# Addon-mapleCUx_HM-RFM69-012.net
KiCad netlist of a schematic drawn in EAGLE
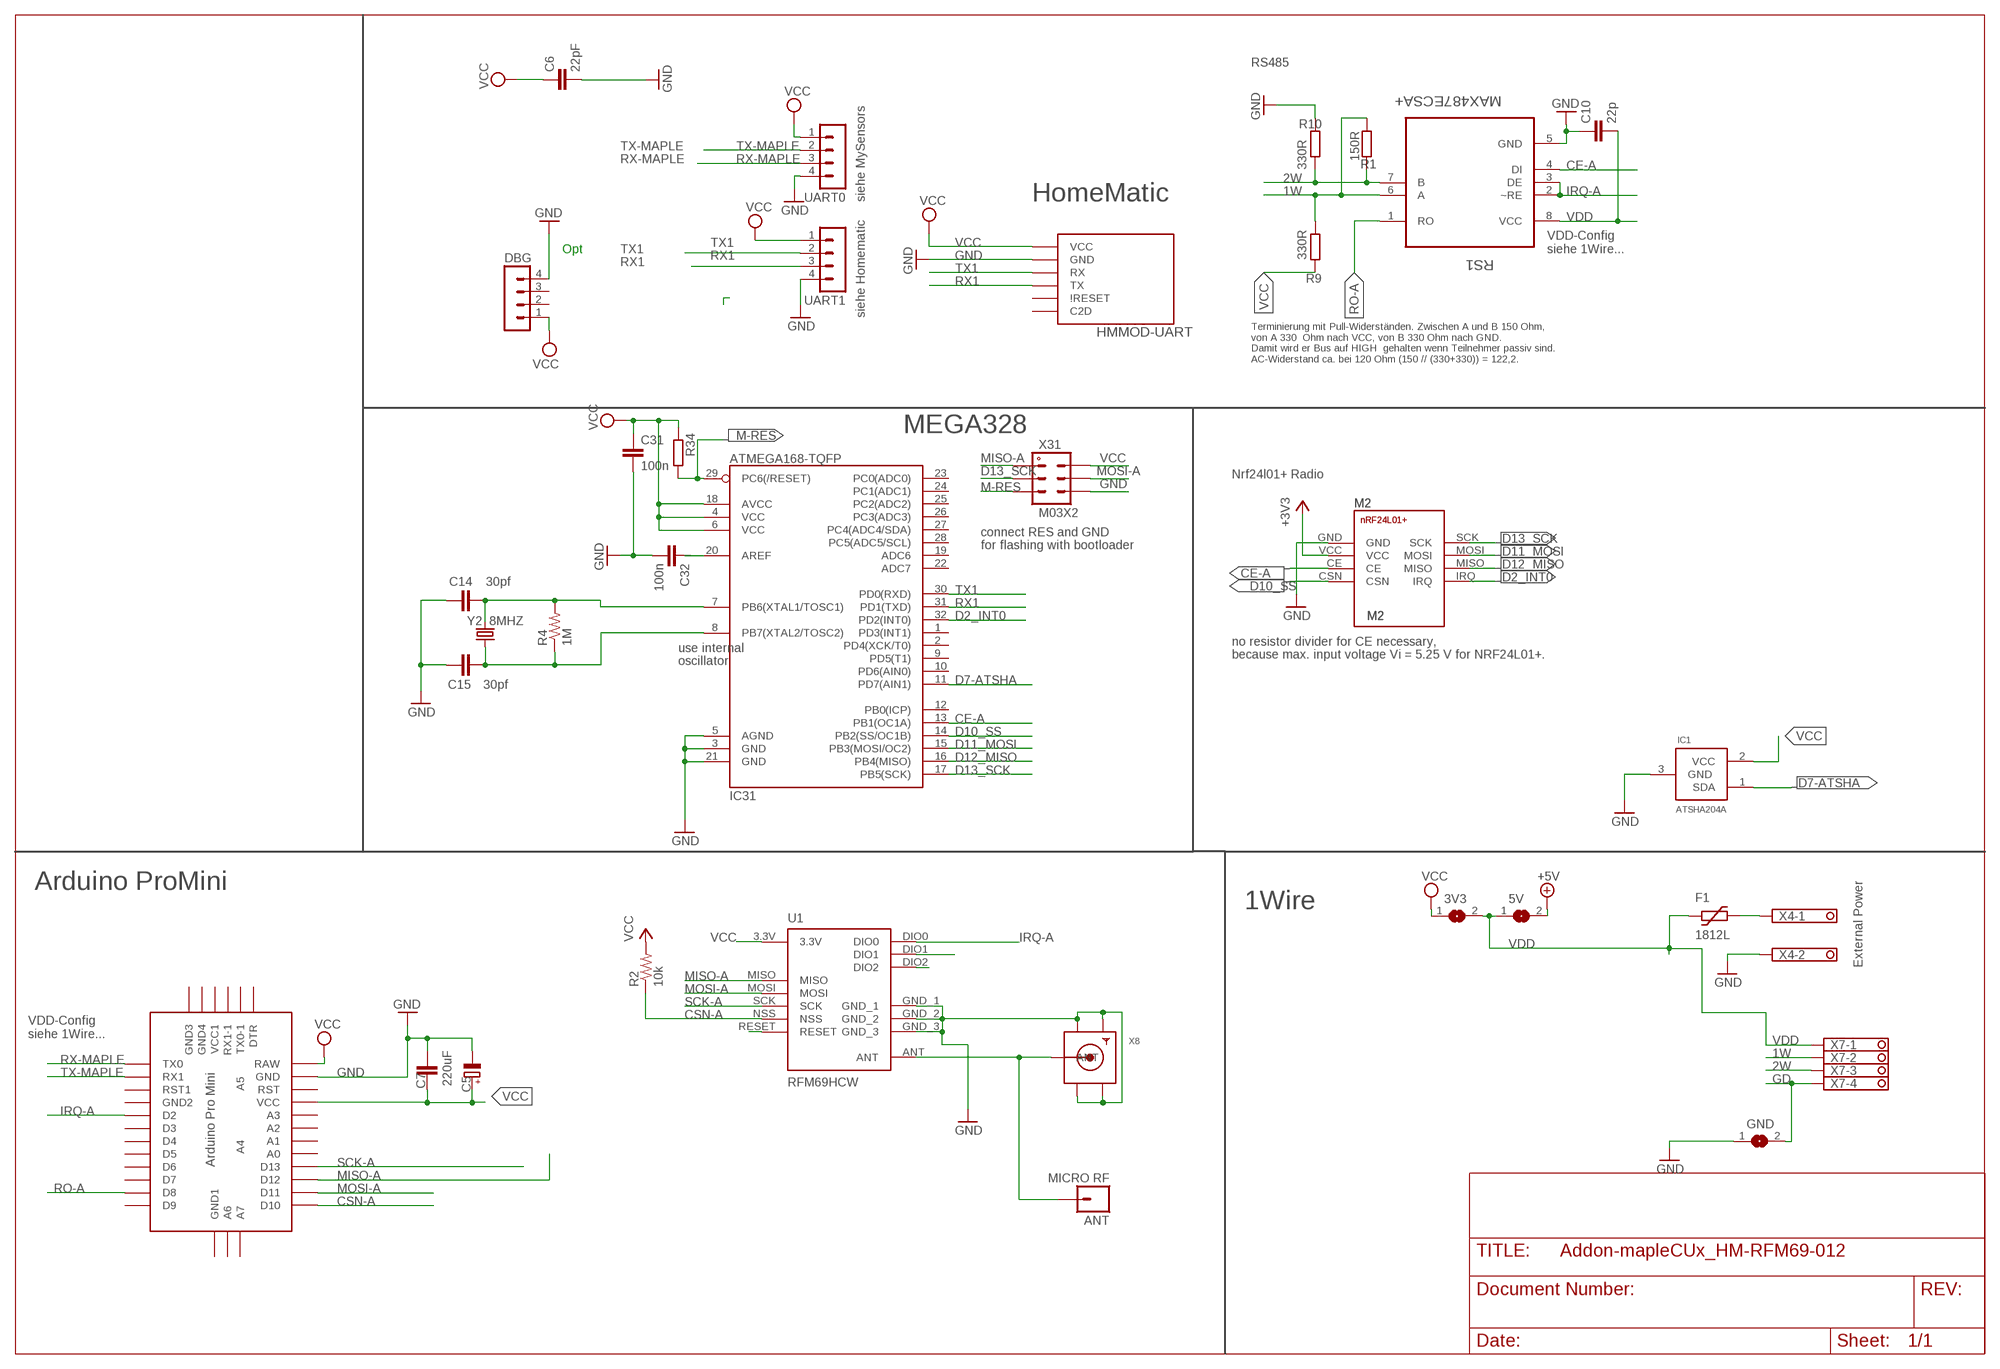
[diagram p0: schematic, sheet 1]

(export (version "E")
  (design (tool "Eeschema 10.0.6"))
  (components
    (comp (ref "3V3") (value "SJ") (footprint "eagle-import:SJ") (libsource (lib "eagle-import") (part "SJ")))
    (comp (ref "5V") (value "SJ") (footprint "eagle-import:SJ") (libsource (lib "eagle-import") (part "SJ")))
    (comp (ref "ANT")
      (value "MICRO RF")
      (footprint "eagle-import:1X01")
      (libsource (lib "eagle-import") (part "M01PTH"))
    )
    (comp (ref "C5")
      (value "220uF")
      (footprint "eagle-import:E5-8,5")
      (libsource (lib "eagle-import") (part "CPOL-EUE5-8.5"))
    )
    (comp (ref "C6")
      (value "22pF")
      (footprint "eagle-import:C0805")
      (libsource (lib "eagle-import") (part "C-EUC0805"))
    )
    (comp (ref "C7")
      (value "C-EUC1812")
      (footprint "eagle-import:C1812")
      (libsource (lib "eagle-import") (part "C-EUC1812"))
    )
    (comp (ref "C10")
      (value "22p")
      (footprint "eagle-import:C0805")
      (libsource (lib "eagle-import") (part "C-EUC0805"))
    )
    (comp (ref "C14")
      (value "30pf")
      (footprint "eagle-import:0805")
      (libsource (lib "eagle-import") (part "CAP0805"))
    )
    (comp (ref "C15")
      (value "30pf")
      (footprint "eagle-import:0805")
      (libsource (lib "eagle-import") (part "CAP0805"))
    )
    (comp (ref "C31")
      (value "100n")
      (footprint "eagle-import:C0805")
      (libsource (lib "eagle-import") (part "C-EUC0805"))
    )
    (comp (ref "C32")
      (value "100n")
      (footprint "eagle-import:C0805")
      (libsource (lib "eagle-import") (part "C-EUC0805"))
    )
    (comp (ref "DBG")
      (value "MA04-1")
      (footprint "eagle-import:MA04-1")
      (libsource (lib "eagle-import") (part "MA04-1"))
    )
    (comp (ref "F1")
      (value "1812L")
      (footprint "eagle-import:1812L")
      (libsource (lib "eagle-import") (part "1812L"))
    )
    (comp (ref "GND") (value "SJ") (footprint "eagle-import:SJ") (libsource (lib "eagle-import") (part "SJ")))
    (comp (ref "HMMOD-UART")
      (value "HM-MOD-UARTDIL")
      (footprint "eagle-import:HM-MOD-UART-DIL")
      (libsource (lib "eagle-import") (part "HM-MOD-UARTDIL"))
    )
    (comp (ref "IC1")
      (value "ATSHA204A")
      (footprint "eagle-import:SOT23")
      (libsource (lib "eagle-import") (part "ATSHA204A"))
    )
    (comp (ref "IC31")
      (value "ATMEGA168-TQFP")
      (footprint "eagle-import:TQFP32-08")
      (libsource (lib "eagle-import") (part "ATMEGA168-TQFP"))
    )
    (comp (ref "M2")
      (value "NRF24L01+SMD")
      (footprint "eagle-import:NRF24L01+SMD")
      (libsource (lib "eagle-import") (part "NRF24L01+SMD"))
    )
    (comp (ref "R1")
      (value "150R")
      (footprint "eagle-import:R0805")
      (libsource (lib "eagle-import") (part "R-EU_R0805"))
    )
    (comp (ref "R2")
      (value "10k")
      (footprint "eagle-import:0805")
      (libsource (lib "eagle-import") (part "RESISTOR0805-RES"))
    )
    (comp (ref "R4")
      (value "1M")
      (footprint "eagle-import:0805")
      (libsource (lib "eagle-import") (part "RESISTOR0805-RES"))
    )
    (comp (ref "R9")
      (value "330R")
      (footprint "eagle-import:R0805")
      (libsource (lib "eagle-import") (part "R-EU_R0805"))
    )
    (comp (ref "R10")
      (value "330R")
      (footprint "eagle-import:R0805")
      (libsource (lib "eagle-import") (part "R-EU_R0805"))
    )
    (comp (ref "R34")
      (value "R-EU_R0805")
      (footprint "eagle-import:R0805")
      (libsource (lib "eagle-import") (part "R-EU_R0805"))
    )
    (comp (ref "RS1")
      (value "MAX487ECSA+")
      (footprint "eagle-import:SOIC127P600X175-8N")
      (libsource (lib "eagle-import") (part "MAX487ECSA+"))
    )
    (comp (ref "U$2")
      (value "ABK-PRO-MINI")
      (footprint "eagle-import:ABK-PRO-MINI")
      (libsource (lib "eagle-import") (part "ABK-PRO-MINI"))
    )
    (comp (ref "U1")
      (value "RFM69HCW")
      (footprint "eagle-import:RFM69HCW-XXXS2")
      (libsource (lib "eagle-import") (part "RFM69HCW"))
    )
    (comp (ref "UART0")
      (value "MA04-1")
      (footprint "eagle-import:MA04-1")
      (libsource (lib "eagle-import") (part "MA04-1"))
    )
    (comp (ref "UART1")
      (value "MA04-1")
      (footprint "eagle-import:MA04-1")
      (libsource (lib "eagle-import") (part "MA04-1"))
    )
    (comp (ref "X4")
      (value "1751248")
      (footprint "eagle-import:1751248")
      (libsource (lib "eagle-import") (part "1751248"))
    )
    (comp (ref "X7")
      (value "1751264")
      (footprint "eagle-import:1751264")
      (libsource (lib "eagle-import") (part "1751264"))
    )
    (comp (ref "X8")
      (value "SMACONNECTOR_EDGE")
      (footprint "eagle-import:SMA_EDGELAUNCH")
      (libsource (lib "eagle-import") (part "SMACONNECTOR_EDGE"))
    )
    (comp (ref "X31")
      (value "M03X2")
      (footprint "eagle-import:2X03-1.27MM_SMD")
      (libsource (lib "eagle-import") (part "M03X2"))
    )
    (comp (ref "Y2")
      (value "8MHZ")
      (footprint "eagle-import:CRYSTAL-TXC-7A")
      (libsource (lib "eagle-import") (part "CRYSTALTXC-7A"))
    )
  )
  (nets
    (net (code "1") (name "+3V3") (class "Default")
      (node (ref "M2") (pin "VCC") (pinfunction "VCC_VCC") (pintype "power_in"))
    )
    (net (code "2") (name "+5V") (class "Default")
      (node (ref "5V") (pin "2") (pinfunction "2_2") (pintype "passive"))
    )
    (net (code "3") (name "/1W") (class "Default")
      (node (ref "R1") (pin "1") (pinfunction "1_1") (pintype "passive"))
      (node (ref "R9") (pin "2") (pinfunction "2_2") (pintype "passive"))
      (node (ref "RS1") (pin "6") (pinfunction "A_6") (pintype "bidirectional"))
      (node (ref "X7") (pin "2") (pinfunction "K_2") (pintype "passive"))
    )
    (net (code "4") (name "/2W") (class "Default")
      (node (ref "R1") (pin "2") (pinfunction "2_2") (pintype "passive"))
      (node (ref "R10") (pin "1") (pinfunction "1_1") (pintype "passive"))
      (node (ref "RS1") (pin "7") (pinfunction "B_7") (pintype "bidirectional"))
      (node (ref "X7") (pin "3") (pinfunction "K_3") (pintype "passive"))
    )
    (net (code "5") (name "/CE-A") (class "Default")
      (node (ref "IC31") (pin "13") (pinfunction "PB1(OC1A)_13") (pintype "bidirectional"))
      (node (ref "M2") (pin "CE") (pinfunction "CE_CE") (pintype "bidirectional"))
      (node (ref "RS1") (pin "4") (pinfunction "DI_4") (pintype "input"))
    )
    (net (code "6") (name "/CSN-A") (class "Default")
      (node (ref "R2") (pin "1") (pinfunction "1_1") (pintype "passive"))
      (node (ref "U$2") (pin "D10") (pinfunction "D10_D10") (pintype "bidirectional"))
      (node (ref "U1") (pin "NSS") (pinfunction "NSS_NSS") (pintype "input"))
    )
    (net (code "7") (name "/D2_INT0") (class "Default")
      (node (ref "IC31") (pin "32") (pinfunction "PD2(INT0)_32") (pintype "bidirectional"))
      (node (ref "M2") (pin "IRQ") (pinfunction "IRQ_IRQ") (pintype "bidirectional"))
    )
    (net (code "8") (name "/D7-ATSHA") (class "Default")
      (node (ref "IC1") (pin "1") (pinfunction "SDA_1") (pintype "bidirectional"))
      (node (ref "IC31") (pin "11") (pinfunction "PD7(AIN1)_11") (pintype "bidirectional"))
    )
    (net (code "9") (name "/D10_SS") (class "Default")
      (node (ref "IC31") (pin "14") (pinfunction "PB2(SS/OC1B)_14") (pintype "bidirectional"))
      (node (ref "M2") (pin "CSN") (pinfunction "CSN_CSN") (pintype "bidirectional"))
    )
    (net (code "10") (name "/D11_MOSI") (class "Default")
      (node (ref "IC31") (pin "15") (pinfunction "PB3(MOSI/OC2)_15") (pintype "bidirectional"))
      (node (ref "M2") (pin "MOSI") (pinfunction "MOSI_MOSI") (pintype "bidirectional"))
    )
    (net (code "11") (name "/D12_MISO") (class "Default")
      (node (ref "IC31") (pin "16") (pinfunction "PB4(MISO)_16") (pintype "bidirectional"))
      (node (ref "M2") (pin "MISO") (pinfunction "MISO_MISO") (pintype "bidirectional"))
    )
    (net (code "12") (name "/D13_SCK") (class "Default")
      (node (ref "IC31") (pin "17") (pinfunction "PB5(SCK)_17") (pintype "bidirectional"))
      (node (ref "M2") (pin "SCK") (pinfunction "SCK_SCK") (pintype "bidirectional"))
      (node (ref "X31") (pin "P$3") (pinfunction "3_P$3") (pintype "passive"))
    )
    (net (code "13") (name "/GD") (class "Default")
      (node (ref "GND") (pin "2") (pinfunction "2_2") (pintype "passive"))
      (node (ref "X7") (pin "4") (pinfunction "K_4") (pintype "passive"))
    )
    (net (code "14") (name "/IRQ-A") (class "Default")
      (node (ref "RS1") (pin "2") (pinfunction "~{RE}_2") (pintype "input"))
      (node (ref "RS1") (pin "3") (pinfunction "DE_3") (pintype "input"))
      (node (ref "U$2") (pin "D2") (pinfunction "D2_D2") (pintype "bidirectional"))
      (node (ref "U1") (pin "DIO0") (pinfunction "DIO0_DIO0") (pintype "bidirectional"))
    )
    (net (code "15") (name "/M-RES") (class "Default")
      (node (ref "IC31") (pin "29") (pinfunction "PC6(/RESET)_29") (pintype "bidirectional"))
      (node (ref "R34") (pin "2") (pinfunction "2_2") (pintype "passive"))
      (node (ref "X31") (pin "P$5") (pinfunction "5_P$5") (pintype "passive"))
    )
    (net (code "16") (name "/MISO-A") (class "Default")
      (node (ref "U$2") (pin "D12") (pinfunction "D12_D12") (pintype "bidirectional"))
      (node (ref "U1") (pin "MISO") (pinfunction "MISO_MISO") (pintype "bidirectional"))
      (node (ref "X31") (pin "P$1") (pinfunction "1_P$1") (pintype "passive"))
    )
    (net (code "17") (name "/MOSI-A") (class "Default")
      (node (ref "U$2") (pin "D11") (pinfunction "D11_D11") (pintype "bidirectional"))
      (node (ref "U1") (pin "MOSI") (pinfunction "MOSI_MOSI") (pintype "input"))
      (node (ref "X31") (pin "P$4") (pinfunction "4_P$4") (pintype "passive"))
    )
    (net (code "18") (name "/RX-MAPLE") (class "Default")
      (node (ref "U$2") (pin "TX0") (pinfunction "TX0_TX0") (pintype "bidirectional"))
      (node (ref "UART0") (pin "3") (pinfunction "3_3") (pintype "passive"))
    )
    (net (code "19") (name "/RX1") (class "Default")
      (node (ref "HMMOD-UART") (pin "5") (pinfunction "TX_5") (pintype "bidirectional"))
      (node (ref "IC31") (pin "31") (pinfunction "PD1(TXD)_31") (pintype "bidirectional"))
      (node (ref "UART1") (pin "3") (pinfunction "3_3") (pintype "passive"))
    )
    (net (code "20") (name "/SCK-A") (class "Default")
      (node (ref "U$2") (pin "D13") (pinfunction "D13_D13") (pintype "bidirectional"))
      (node (ref "U1") (pin "SCK") (pinfunction "SCK_SCK") (pintype "input"))
    )
    (net (code "21") (name "/TX-MAPLE") (class "Default")
      (node (ref "U$2") (pin "RX1") (pinfunction "RX1_RX1") (pintype "bidirectional"))
      (node (ref "UART0") (pin "2") (pinfunction "2_2") (pintype "passive"))
    )
    (net (code "22") (name "/TX1") (class "Default")
      (node (ref "HMMOD-UART") (pin "6") (pinfunction "RX_6") (pintype "bidirectional"))
      (node (ref "IC31") (pin "30") (pinfunction "PD0(RXD)_30") (pintype "bidirectional"))
      (node (ref "UART1") (pin "2") (pinfunction "2_2") (pintype "passive"))
    )
    (net (code "23") (name "/VDD") (class "Default")
      (node (ref "3V3") (pin "2") (pinfunction "2_2") (pintype "passive"))
      (node (ref "5V") (pin "1") (pinfunction "1_1") (pintype "passive"))
      (node (ref "C10") (pin "2") (pinfunction "2_2") (pintype "passive"))
      (node (ref "F1") (pin "P$1") (pinfunction "1_P$1") (pintype "passive"))
      (node (ref "RS1") (pin "8") (pinfunction "VCC_8") (pintype "power_in"))
      (node (ref "X7") (pin "1") (pinfunction "K_1") (pintype "passive"))
    )
    (net (code "24") (name "GND") (class "Default")
      (node (ref "C10") (pin "1") (pinfunction "1_1") (pintype "passive"))
      (node (ref "C14") (pin "1") (pinfunction "1_1") (pintype "passive"))
      (node (ref "C15") (pin "1") (pinfunction "1_1") (pintype "passive"))
      (node (ref "C31") (pin "2") (pinfunction "2_2") (pintype "passive"))
      (node (ref "C32") (pin "2") (pinfunction "2_2") (pintype "passive"))
      (node (ref "C5") (pin "-") (pinfunction "-_-") (pintype "passive"))
      (node (ref "C6") (pin "2") (pinfunction "2_2") (pintype "passive"))
      (node (ref "C7") (pin "1") (pinfunction "1_1") (pintype "passive"))
      (node (ref "DBG") (pin "4") (pinfunction "4_4") (pintype "passive"))
      (node (ref "GND") (pin "1") (pinfunction "1_1") (pintype "passive"))
      (node (ref "HMMOD-UART") (pin "2") (pinfunction "GND_2") (pintype "power_in"))
      (node (ref "IC1") (pin "3") (pinfunction "GND_3") (pintype "bidirectional"))
      (node (ref "IC31") (pin "21") (pinfunction "GND_21") (pintype "bidirectional"))
      (node (ref "IC31") (pin "3") (pinfunction "GND_3") (pintype "bidirectional"))
      (node (ref "IC31") (pin "5") (pinfunction "AGND_5") (pintype "bidirectional"))
      (node (ref "M2") (pin "GND") (pinfunction "GND_GND") (pintype "power_in"))
      (node (ref "R10") (pin "2") (pinfunction "2_2") (pintype "passive"))
      (node (ref "RS1") (pin "5") (pinfunction "GND_5") (pintype "passive"))
      (node (ref "U$2") (pin "GND") (pinfunction "GND_GND") (pintype "bidirectional"))
      (node (ref "U1") (pin "GND_1") (pinfunction "GND_1_GND_1") (pintype "power_in"))
      (node (ref "U1") (pin "GND_2") (pinfunction "GND_2_GND_2") (pintype "power_in"))
      (node (ref "U1") (pin "GND_3") (pinfunction "GND_3_GND_3") (pintype "power_in"))
      (node (ref "UART0") (pin "4") (pinfunction "4_4") (pintype "passive"))
      (node (ref "UART1") (pin "4") (pinfunction "4_4") (pintype "passive"))
      (node (ref "X31") (pin "P$6") (pinfunction "6_P$6") (pintype "passive"))
      (node (ref "X4") (pin "2") (pinfunction "K_2") (pintype "passive"))
      (node (ref "X8") (pin "GND@1") (pinfunction "GND4_GND@1") (pintype "power_in"))
      (node (ref "X8") (pin "GND@2") (pinfunction "GND3_GND@2") (pintype "power_in"))
      (node (ref "X8") (pin "GND@3") (pinfunction "GND2_GND@3") (pintype "power_in"))
      (node (ref "X8") (pin "GND@4") (pinfunction "GND1_GND@4") (pintype "power_in"))
    )
    (net (code "25") (name "Net-(F1-2)") (class "Default")
      (node (ref "F1") (pin "P$2") (pinfunction "2_P$2") (pintype "passive"))
      (node (ref "X4") (pin "1") (pinfunction "K_1") (pintype "passive"))
    )
    (net (code "26") (name "Net-(IC31-AREF)") (class "Default")
      (node (ref "C32") (pin "1") (pinfunction "1_1") (pintype "passive"))
      (node (ref "IC31") (pin "20") (pinfunction "AREF_20") (pintype "bidirectional"))
    )
    (net (code "27") (name "Net-(IC31-PB6(XTAL1{slash}TOSC1))") (class "Default")
      (node (ref "C14") (pin "2") (pinfunction "2_2") (pintype "passive"))
      (node (ref "IC31") (pin "7") (pinfunction "PB6(XTAL1/TOSC1)_7") (pintype "bidirectional"))
      (node (ref "R4") (pin "2") (pinfunction "2_2") (pintype "passive"))
      (node (ref "Y2") (pin "P$2") (pinfunction "2_P$2") (pintype "passive"))
    )
    (net (code "28") (name "Net-(IC31-PB7(XTAL2{slash}TOSC2))") (class "Default")
      (node (ref "C15") (pin "2") (pinfunction "2_2") (pintype "passive"))
      (node (ref "IC31") (pin "8") (pinfunction "PB7(XTAL2/TOSC2)_8") (pintype "bidirectional"))
      (node (ref "R4") (pin "1") (pinfunction "1_1") (pintype "passive"))
      (node (ref "Y2") (pin "P$1") (pinfunction "1_P$1") (pintype "passive"))
    )
    (net (code "29") (name "Net-(X8-ANT)") (class "Default")
      (node (ref "ANT") (pin "1") (pinfunction "1_1") (pintype "passive"))
      (node (ref "U1") (pin "ANT") (pinfunction "ANT_ANT") (pintype "passive"))
      (node (ref "X8") (pin "P") (pinfunction "ANT_P") (pintype "bidirectional"))
    )
    (net (code "30") (name "RO-A") (class "Default")
      (node (ref "RS1") (pin "1") (pinfunction "RO_1") (pintype "output"))
      (node (ref "U$2") (pin "D8") (pinfunction "D8_D8") (pintype "bidirectional"))
    )
    (net (code "31") (name "VCC") (class "Default")
      (node (ref "3V3") (pin "1") (pinfunction "1_1") (pintype "passive"))
      (node (ref "C31") (pin "1") (pinfunction "1_1") (pintype "passive"))
      (node (ref "C5") (pin "+") (pinfunction "+_+") (pintype "passive"))
      (node (ref "C6") (pin "1") (pinfunction "1_1") (pintype "passive"))
      (node (ref "C7") (pin "2") (pinfunction "2_2") (pintype "passive"))
      (node (ref "DBG") (pin "1") (pinfunction "1_1") (pintype "passive"))
      (node (ref "HMMOD-UART") (pin "1") (pinfunction "VCC_1") (pintype "power_in"))
      (node (ref "IC1") (pin "2") (pinfunction "VCC_2") (pintype "bidirectional"))
      (node (ref "IC31") (pin "18") (pinfunction "AVCC_18") (pintype "bidirectional"))
      (node (ref "IC31") (pin "4") (pinfunction "VCC_4") (pintype "bidirectional"))
      (node (ref "IC31") (pin "6") (pinfunction "VCC_6") (pintype "bidirectional"))
      (node (ref "R2") (pin "2") (pinfunction "2_2") (pintype "passive"))
      (node (ref "R34") (pin "1") (pinfunction "1_1") (pintype "passive"))
      (node (ref "R9") (pin "1") (pinfunction "1_1") (pintype "passive"))
      (node (ref "U$2") (pin "RAW") (pinfunction "RAW_RAW") (pintype "bidirectional"))
      (node (ref "U$2") (pin "VCC") (pinfunction "VCC_VCC") (pintype "bidirectional"))
      (node (ref "U1") (pin "3.3V") (pinfunction "3.3V_3.3V") (pintype "power_in"))
      (node (ref "UART0") (pin "1") (pinfunction "1_1") (pintype "passive"))
      (node (ref "UART1") (pin "1") (pinfunction "1_1") (pintype "passive"))
      (node (ref "X31") (pin "P$2") (pinfunction "2_P$2") (pintype "passive"))
    )
    (net (code "32") (name "unconnected-(DBG-Pad2)") (class "Default")
      (node (ref "DBG") (pin "2") (pinfunction "2_2") (pintype "passive"))
    )
    (net (code "33") (name "unconnected-(DBG-Pad3)") (class "Default")
      (node (ref "DBG") (pin "3") (pinfunction "3_3") (pintype "passive"))
    )
    (net (code "34") (name "unconnected-(HMMOD-UART-C2D-Pad3)") (class "Default")
      (node (ref "HMMOD-UART") (pin "3") (pinfunction "C2D_3") (pintype "bidirectional"))
    )
    (net (code "35") (name "unconnected-(HMMOD-UART-\\~{RESET}-Pad4)") (class "Default")
      (node (ref "HMMOD-UART") (pin "4") (pinfunction "\\~{RESET}_4") (pintype "bidirectional"))
    )
    (net (code "36") (name "unconnected-(IC31-ADC6-Pad19)") (class "Default")
      (node (ref "IC31") (pin "19") (pinfunction "ADC6_19") (pintype "bidirectional"))
    )
    (net (code "37") (name "unconnected-(IC31-ADC7-Pad22)") (class "Default")
      (node (ref "IC31") (pin "22") (pinfunction "ADC7_22") (pintype "bidirectional"))
    )
    (net (code "38") (name "unconnected-(IC31-PB0(ICP)-Pad12)") (class "Default")
      (node (ref "IC31") (pin "12") (pinfunction "PB0(ICP)_12") (pintype "bidirectional"))
    )
    (net (code "39") (name "unconnected-(IC31-PC0(ADC0)-Pad23)") (class "Default")
      (node (ref "IC31") (pin "23") (pinfunction "PC0(ADC0)_23") (pintype "bidirectional"))
    )
    (net (code "40") (name "unconnected-(IC31-PC1(ADC1)-Pad24)") (class "Default")
      (node (ref "IC31") (pin "24") (pinfunction "PC1(ADC1)_24") (pintype "bidirectional"))
    )
    (net (code "41") (name "unconnected-(IC31-PC2(ADC2)-Pad25)") (class "Default")
      (node (ref "IC31") (pin "25") (pinfunction "PC2(ADC2)_25") (pintype "bidirectional"))
    )
    (net (code "42") (name "unconnected-(IC31-PC3(ADC3)-Pad26)") (class "Default")
      (node (ref "IC31") (pin "26") (pinfunction "PC3(ADC3)_26") (pintype "bidirectional"))
    )
    (net (code "43") (name "unconnected-(IC31-PC4(ADC4{slash}SDA)-Pad27)") (class "Default")
      (node (ref "IC31") (pin "27") (pinfunction "PC4(ADC4/SDA)_27") (pintype "bidirectional"))
    )
    (net (code "44") (name "unconnected-(IC31-PC5(ADC5{slash}SCL)-Pad28)") (class "Default")
      (node (ref "IC31") (pin "28") (pinfunction "PC5(ADC5/SCL)_28") (pintype "bidirectional"))
    )
    (net (code "45") (name "unconnected-(IC31-PD3(INT1)-Pad1)") (class "Default")
      (node (ref "IC31") (pin "1") (pinfunction "PD3(INT1)_1") (pintype "bidirectional"))
    )
    (net (code "46") (name "unconnected-(IC31-PD4(XCK{slash}T0)-Pad2)") (class "Default")
      (node (ref "IC31") (pin "2") (pinfunction "PD4(XCK/T0)_2") (pintype "bidirectional"))
    )
    (net (code "47") (name "unconnected-(IC31-PD5(T1)-Pad9)") (class "Default")
      (node (ref "IC31") (pin "9") (pinfunction "PD5(T1)_9") (pintype "bidirectional"))
    )
    (net (code "48") (name "unconnected-(IC31-PD6(AIN0)-Pad10)") (class "Default")
      (node (ref "IC31") (pin "10") (pinfunction "PD6(AIN0)_10") (pintype "bidirectional"))
    )
    (net (code "49") (name "unconnected-(U$2-GND1-PadGND4)") (class "Default")
      (node (ref "U$2") (pin "GND4") (pinfunction "GND1_GND4") (pintype "bidirectional"))
    )
    (net (code "50") (name "unconnected-(U$2-GND2-PadGND1)") (class "Default")
      (node (ref "U$2") (pin "GND1") (pinfunction "GND2_GND1") (pintype "bidirectional"))
    )
    (net (code "51") (name "unconnected-(U$2-GND3-PadGND2)") (class "Default")
      (node (ref "U$2") (pin "GND2") (pinfunction "GND3_GND2") (pintype "bidirectional"))
    )
    (net (code "52") (name "unconnected-(U$2-GND4-PadGND3)") (class "Default")
      (node (ref "U$2") (pin "GND3") (pinfunction "GND4_GND3") (pintype "bidirectional"))
    )
    (net (code "53") (name "unconnected-(U$2-PadA0)") (class "Default")
      (node (ref "U$2") (pin "A0") (pinfunction "A0_A0") (pintype "bidirectional"))
    )
    (net (code "54") (name "unconnected-(U$2-PadA1)") (class "Default")
      (node (ref "U$2") (pin "A1") (pinfunction "A1_A1") (pintype "bidirectional"))
    )
    (net (code "55") (name "unconnected-(U$2-PadA2)") (class "Default")
      (node (ref "U$2") (pin "A2") (pinfunction "A2_A2") (pintype "bidirectional"))
    )
    (net (code "56") (name "unconnected-(U$2-PadA3)") (class "Default")
      (node (ref "U$2") (pin "A3") (pinfunction "A3_A3") (pintype "bidirectional"))
    )
    (net (code "57") (name "unconnected-(U$2-PadA4)") (class "Default")
      (node (ref "U$2") (pin "A4") (pinfunction "A4_A4") (pintype "bidirectional"))
    )
    (net (code "58") (name "unconnected-(U$2-PadA5)") (class "Default")
      (node (ref "U$2") (pin "A5") (pinfunction "A5_A5") (pintype "bidirectional"))
    )
    (net (code "59") (name "unconnected-(U$2-PadA6)") (class "Default")
      (node (ref "U$2") (pin "A6") (pinfunction "A6_A6") (pintype "bidirectional"))
    )
    (net (code "60") (name "unconnected-(U$2-PadA7)") (class "Default")
      (node (ref "U$2") (pin "A7") (pinfunction "A7_A7") (pintype "bidirectional"))
    )
    (net (code "61") (name "unconnected-(U$2-PadD3)") (class "Default")
      (node (ref "U$2") (pin "D3") (pinfunction "D3_D3") (pintype "bidirectional"))
    )
    (net (code "62") (name "unconnected-(U$2-PadD4)") (class "Default")
      (node (ref "U$2") (pin "D4") (pinfunction "D4_D4") (pintype "bidirectional"))
    )
    (net (code "63") (name "unconnected-(U$2-PadD5)") (class "Default")
      (node (ref "U$2") (pin "D5") (pinfunction "D5_D5") (pintype "bidirectional"))
    )
    (net (code "64") (name "unconnected-(U$2-PadD6)") (class "Default")
      (node (ref "U$2") (pin "D6") (pinfunction "D6_D6") (pintype "bidirectional"))
    )
    (net (code "65") (name "unconnected-(U$2-PadD7)") (class "Default")
      (node (ref "U$2") (pin "D7") (pinfunction "D7_D7") (pintype "bidirectional"))
    )
    (net (code "66") (name "unconnected-(U$2-PadD9)") (class "Default")
      (node (ref "U$2") (pin "D9") (pinfunction "D9_D9") (pintype "bidirectional"))
    )
    (net (code "67") (name "unconnected-(U$2-PadDTR)") (class "Default")
      (node (ref "U$2") (pin "DTR") (pinfunction "DTR_DTR") (pintype "bidirectional"))
    )
    (net (code "68") (name "unconnected-(U$2-PadRST)") (class "Default")
      (node (ref "U$2") (pin "RST") (pinfunction "RST_RST") (pintype "bidirectional"))
    )
    (net (code "69") (name "unconnected-(U$2-PadRST1)") (class "Default")
      (node (ref "U$2") (pin "RST1") (pinfunction "RST1_RST1") (pintype "bidirectional"))
    )
    (net (code "70") (name "unconnected-(U$2-PadRX1-1)") (class "Default")
      (node (ref "U$2") (pin "RX1-1") (pinfunction "RX1-1_RX1-1") (pintype "bidirectional"))
    )
    (net (code "71") (name "unconnected-(U$2-PadTX0-1)") (class "Default")
      (node (ref "U$2") (pin "TX0-1") (pinfunction "TX0-1_TX0-1") (pintype "bidirectional"))
    )
    (net (code "72") (name "unconnected-(U$2-PadVCC1)") (class "Default")
      (node (ref "U$2") (pin "VCC1") (pinfunction "VCC1_VCC1") (pintype "bidirectional"))
    )
    (net (code "73") (name "unconnected-(U1-PadDIO1)") (class "Default")
      (node (ref "U1") (pin "DIO1") (pinfunction "DIO1_DIO1") (pintype "bidirectional"))
    )
    (net (code "74") (name "unconnected-(U1-PadDIO2)") (class "Default")
      (node (ref "U1") (pin "DIO2") (pinfunction "DIO2_DIO2") (pintype "bidirectional"))
    )
    (net (code "75") (name "unconnected-(U1-PadRESET)") (class "Default")
      (node (ref "U1") (pin "RESET") (pinfunction "RESET_RESET") (pintype "input"))
    )
  )
)
